# UTN-ESINT01.net
KiCad netlist of a schematic drawn in EAGLE
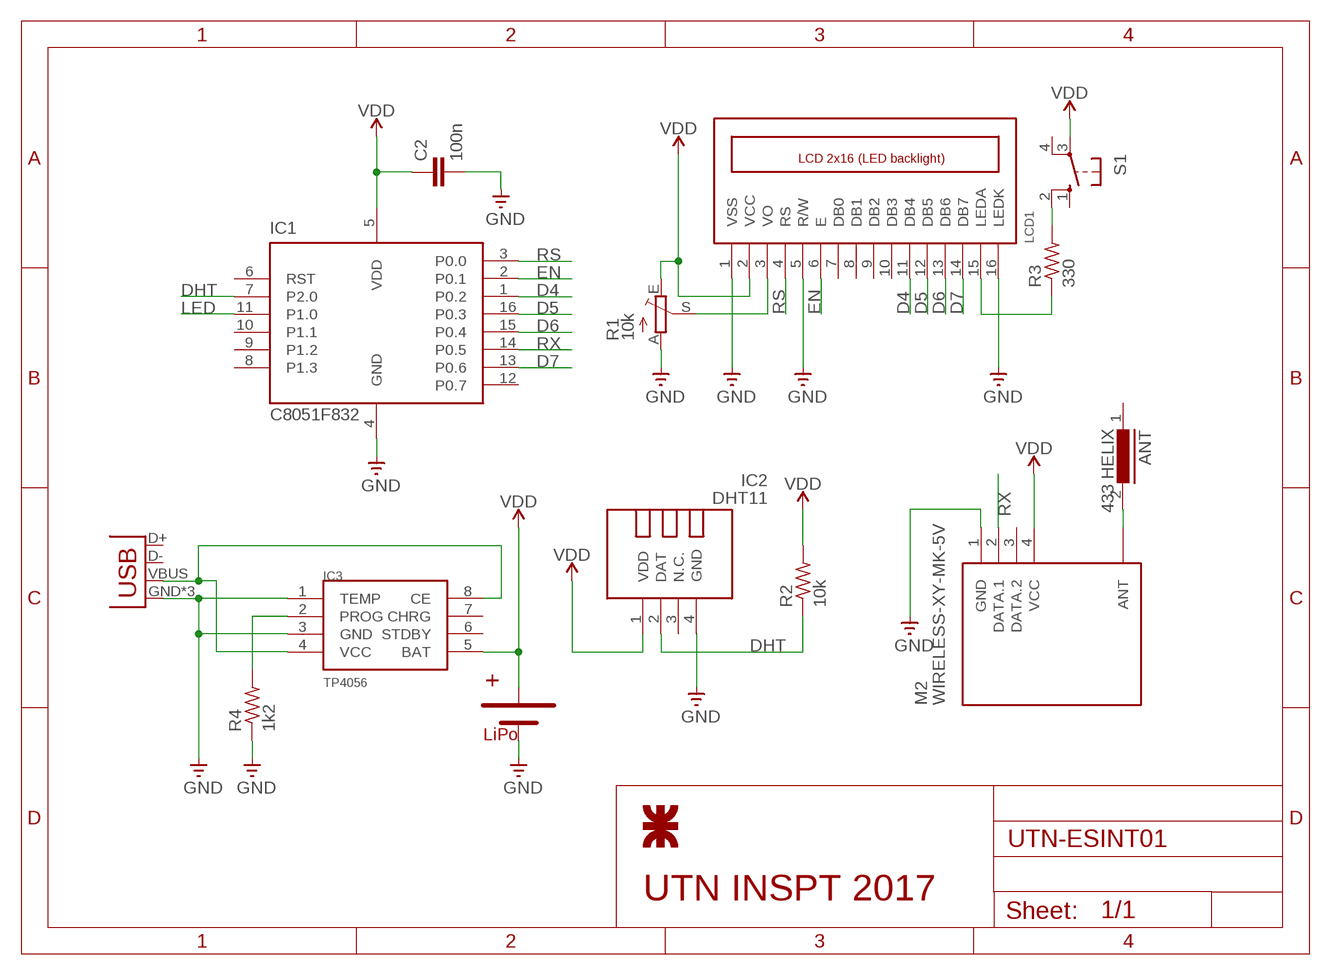
[diagram p0: schematic, sheet 1]

(export (version "E")
  (design (tool "Eeschema 10.0.6"))
  (components
    (comp (ref "ANT")
      (value "433 HELIX")
      (footprint "eagle-import:SMSC20")
      (libsource (lib "eagle-import") (part "SMSC20"))
    )
    (comp (ref "C2")
      (value "100n")
      (footprint "eagle-import:C050-024X044")
      (libsource (lib "eagle-import") (part "C-EU050-024X044"))
    )
    (comp (ref "IC1")
      (value "C8051F832")
      (footprint "eagle-import:SOIC16R")
      (libsource (lib "eagle-import") (part "C8051F832"))
    )
    (comp (ref "IC2")
      (value "DHT11")
      (footprint "eagle-import:TEMP-HUM-SENSOR-DHT11")
      (libsource (lib "eagle-import") (part "TEMP-HUM-SENSOR-DHT11"))
    )
    (comp (ref "IC3")
      (value "TP4056")
      (footprint "eagle-import:SOP-8")
      (libsource (lib "eagle-import") (part "TP4056"))
    )
    (comp (ref "LCD1")
      (value "LCD_2X16_SIL")
      (footprint "eagle-import:HY-1602F")
      (libsource (lib "eagle-import") (part "LCD_2X16_SIL"))
    )
    (comp (ref "M2")
      (value "WIRELESS-XY-MK-5V")
      (footprint "eagle-import:WIRELESS-XY-MK-5V")
      (libsource (lib "eagle-import") (part "WIRELESS-XY-MK-5V"))
    )
    (comp (ref "R1")
      (value "10k")
      (footprint "eagle-import:B64Y")
      (libsource (lib "eagle-import") (part "TRIM_EU-B64Y"))
    )
    (comp (ref "R2")
      (value "10k")
      (footprint "eagle-import:0207_10")
      (libsource (lib "eagle-import") (part "R-US_0207/10"))
    )
    (comp (ref "R3")
      (value "330")
      (footprint "eagle-import:0207_10")
      (libsource (lib "eagle-import") (part "R-US_0207/10"))
    )
    (comp (ref "R4")
      (value "1k2")
      (footprint "eagle-import:0207_10")
      (libsource (lib "eagle-import") (part "R-US_0207/10"))
    )
    (comp (ref "S1")
      (value "10-XX")
      (footprint "eagle-import:B3F-10XX")
      (fields (field (name "MPN") "B3F-1000"))
      (libsource (lib "eagle-import") (part "10-XX"))
    )
    (comp (ref "U$3")
      (value "UTN_LOGO")
      (footprint "eagle-import:UTN_LOGO")
      (libsource (lib "eagle-import") (part "UTN_LOGO"))
    )
    (comp (ref "U$4")
      (value "LiPo")
      (footprint "eagle-import:BATTERYPAD")
      (libsource (lib "eagle-import") (part "BATTERYPAD"))
    )
    (comp (ref "X1")
      (value "USB-MICROB")
      (footprint "eagle-import:USB-MICROB")
      (libsource (lib "eagle-import") (part "USB-MICROB"))
    )
  )
  (nets
    (net (code "1") (name "/D4") (class "Default")
      (node (ref "IC1") (pin "1") (pinfunction "P0.2_1") (pintype "bidirectional"))
      (node (ref "LCD1") (pin "11") (pinfunction "DB4_11") (pintype "bidirectional"))
    )
    (net (code "2") (name "/D5") (class "Default")
      (node (ref "IC1") (pin "16") (pinfunction "P0.3_16") (pintype "bidirectional"))
      (node (ref "LCD1") (pin "12") (pinfunction "DB5_12") (pintype "bidirectional"))
    )
    (net (code "3") (name "/D6") (class "Default")
      (node (ref "IC1") (pin "15") (pinfunction "P0.4_15") (pintype "bidirectional"))
      (node (ref "LCD1") (pin "13") (pinfunction "DB6_13") (pintype "bidirectional"))
    )
    (net (code "4") (name "/D7") (class "Default")
      (node (ref "IC1") (pin "13") (pinfunction "P0.6_13") (pintype "bidirectional"))
      (node (ref "LCD1") (pin "14") (pinfunction "DB7_14") (pintype "bidirectional"))
    )
    (net (code "5") (name "/DHT") (class "Default")
      (node (ref "IC1") (pin "7") (pinfunction "P2.0_7") (pintype "bidirectional"))
      (node (ref "IC2") (pin "2") (pinfunction "DAT_2") (pintype "bidirectional"))
      (node (ref "R2") (pin "1") (pinfunction "1_1") (pintype "passive"))
    )
    (net (code "6") (name "/EN") (class "Default")
      (node (ref "IC1") (pin "2") (pinfunction "P0.1_2") (pintype "bidirectional"))
      (node (ref "LCD1") (pin "6") (pinfunction "E_6") (pintype "input"))
    )
    (net (code "7") (name "/LED") (class "Default")
      (node (ref "IC1") (pin "11") (pinfunction "P1.0_11") (pintype "bidirectional"))
    )
    (net (code "8") (name "/RS") (class "Default")
      (node (ref "IC1") (pin "3") (pinfunction "P0.0_3") (pintype "bidirectional"))
      (node (ref "LCD1") (pin "4") (pinfunction "RS_4") (pintype "input"))
    )
    (net (code "9") (name "/RX") (class "Default")
      (node (ref "IC1") (pin "14") (pinfunction "P0.5_14") (pintype "bidirectional"))
      (node (ref "M2") (pin "2") (pinfunction "DATA.1_2") (pintype "bidirectional"))
    )
    (net (code "10") (name "GND") (class "Default")
      (node (ref "C2") (pin "2") (pinfunction "2_2") (pintype "passive"))
      (node (ref "IC1") (pin "4") (pinfunction "GND_4") (pintype "bidirectional"))
      (node (ref "IC2") (pin "4") (pinfunction "GND_4") (pintype "power_in"))
      (node (ref "IC3") (pin "1") (pinfunction "TEMP_1") (pintype "bidirectional"))
      (node (ref "IC3") (pin "3") (pinfunction "GND_3") (pintype "bidirectional"))
      (node (ref "LCD1") (pin "1") (pinfunction "VSS_1") (pintype "power_in"))
      (node (ref "LCD1") (pin "16") (pinfunction "LEDK_16") (pintype "passive"))
      (node (ref "LCD1") (pin "5") (pinfunction "R/W_5") (pintype "input"))
      (node (ref "M2") (pin "1") (pinfunction "GND_1") (pintype "bidirectional"))
      (node (ref "R1") (pin "A") (pinfunction "A_A") (pintype "passive"))
      (node (ref "R4") (pin "1") (pinfunction "1_1") (pintype "passive"))
      (node (ref "U$4") (pin "-VE") (pinfunction "-VE_-VE") (pintype "power_in"))
      (node (ref "X1") (pin "GND") (pinfunction "GND_GND") (pintype "bidirectional"))
      (node (ref "X1") (pin "MT1") (pinfunction "GND_MT1") (pintype "bidirectional"))
      (node (ref "X1") (pin "MT2") (pinfunction "GND_MT2") (pintype "bidirectional"))
    )
    (net (code "11") (name "Net-(ANT-Pad2)") (class "Default")
      (node (ref "ANT") (pin "2") (pinfunction "2_2") (pintype "passive"))
      (node (ref "M2") (pin "ANT") (pinfunction "ANT_ANT") (pintype "output"))
    )
    (net (code "12") (name "Net-(IC3-CE)") (class "Default")
      (node (ref "IC3") (pin "4") (pinfunction "VCC_4") (pintype "bidirectional"))
      (node (ref "IC3") (pin "8") (pinfunction "CE_8") (pintype "bidirectional"))
      (node (ref "X1") (pin "VBUS") (pinfunction "VBUS_VBUS") (pintype "bidirectional"))
    )
    (net (code "13") (name "Net-(IC3-PROG)") (class "Default")
      (node (ref "IC3") (pin "2") (pinfunction "PROG_2") (pintype "bidirectional"))
      (node (ref "R4") (pin "2") (pinfunction "2_2") (pintype "passive"))
    )
    (net (code "14") (name "Net-(LCD1-LEDA)") (class "Default")
      (node (ref "LCD1") (pin "15") (pinfunction "LEDA_15") (pintype "passive"))
      (node (ref "R3") (pin "1") (pinfunction "1_1") (pintype "passive"))
    )
    (net (code "15") (name "Net-(LCD1-VO)") (class "Default")
      (node (ref "LCD1") (pin "3") (pinfunction "VO_3") (pintype "input"))
      (node (ref "R1") (pin "S") (pinfunction "S_S") (pintype "passive"))
    )
    (net (code "16") (name "Net-(S1-S1)") (class "Default")
      (node (ref "R3") (pin "2") (pinfunction "2_2") (pintype "passive"))
      (node (ref "S1") (pin "2") (pinfunction "S1_2") (pintype "passive"))
    )
    (net (code "17") (name "VDD") (class "Default")
      (node (ref "C2") (pin "1") (pinfunction "1_1") (pintype "passive"))
      (node (ref "IC1") (pin "5") (pinfunction "VDD_5") (pintype "bidirectional"))
      (node (ref "IC2") (pin "1") (pinfunction "VDD_1") (pintype "power_in"))
      (node (ref "IC3") (pin "5") (pinfunction "BAT_5") (pintype "bidirectional"))
      (node (ref "LCD1") (pin "2") (pinfunction "VCC_2") (pintype "power_in"))
      (node (ref "M2") (pin "4") (pinfunction "VCC_4") (pintype "bidirectional"))
      (node (ref "R1") (pin "E") (pinfunction "E_E") (pintype "passive"))
      (node (ref "R2") (pin "2") (pinfunction "2_2") (pintype "passive"))
      (node (ref "S1") (pin "3") (pinfunction "P_3") (pintype "passive"))
      (node (ref "U$4") (pin "+VE") (pinfunction "+VE_+VE") (pintype "power_in"))
    )
    (net (code "18") (name "unconnected-(ANT-Pad1)") (class "Default")
      (node (ref "ANT") (pin "1") (pinfunction "1_1") (pintype "passive"))
    )
    (net (code "19") (name "unconnected-(IC1-P0.7-Pad12)") (class "Default")
      (node (ref "IC1") (pin "12") (pinfunction "P0.7_12") (pintype "bidirectional"))
    )
    (net (code "20") (name "unconnected-(IC1-P1.1-Pad10)") (class "Default")
      (node (ref "IC1") (pin "10") (pinfunction "P1.1_10") (pintype "bidirectional"))
    )
    (net (code "21") (name "unconnected-(IC1-P1.2-Pad9)") (class "Default")
      (node (ref "IC1") (pin "9") (pinfunction "P1.2_9") (pintype "bidirectional"))
    )
    (net (code "22") (name "unconnected-(IC1-P1.3-Pad8)") (class "Default")
      (node (ref "IC1") (pin "8") (pinfunction "P1.3_8") (pintype "bidirectional"))
    )
    (net (code "23") (name "unconnected-(IC1-RST-Pad6)") (class "Default")
      (node (ref "IC1") (pin "6") (pinfunction "RST_6") (pintype "bidirectional"))
    )
    (net (code "24") (name "unconnected-(IC2-N.C.-Pad3)") (class "Default")
      (node (ref "IC2") (pin "3") (pinfunction "N.C._3") (pintype "passive"))
    )
    (net (code "25") (name "unconnected-(IC3-CHRG-Pad7)") (class "Default")
      (node (ref "IC3") (pin "7") (pinfunction "CHRG_7") (pintype "bidirectional"))
    )
    (net (code "26") (name "unconnected-(IC3-STDBY-Pad6)") (class "Default")
      (node (ref "IC3") (pin "6") (pinfunction "STDBY_6") (pintype "bidirectional"))
    )
    (net (code "27") (name "unconnected-(LCD1-DB0-Pad7)") (class "Default")
      (node (ref "LCD1") (pin "7") (pinfunction "DB0_7") (pintype "bidirectional"))
    )
    (net (code "28") (name "unconnected-(LCD1-DB1-Pad8)") (class "Default")
      (node (ref "LCD1") (pin "8") (pinfunction "DB1_8") (pintype "bidirectional"))
    )
    (net (code "29") (name "unconnected-(LCD1-DB2-Pad9)") (class "Default")
      (node (ref "LCD1") (pin "9") (pinfunction "DB2_9") (pintype "bidirectional"))
    )
    (net (code "30") (name "unconnected-(LCD1-DB3-Pad10)") (class "Default")
      (node (ref "LCD1") (pin "10") (pinfunction "DB3_10") (pintype "bidirectional"))
    )
    (net (code "31") (name "unconnected-(M2-DATA.2-Pad3)") (class "Default")
      (node (ref "M2") (pin "3") (pinfunction "DATA.2_3") (pintype "bidirectional"))
    )
    (net (code "32") (name "unconnected-(S1-P1-Pad4)") (class "Default")
      (node (ref "S1") (pin "4") (pinfunction "P1_4") (pintype "passive"))
    )
    (net (code "33") (name "unconnected-(S1-S-Pad1)") (class "Default")
      (node (ref "S1") (pin "1") (pinfunction "S_1") (pintype "passive"))
    )
    (net (code "34") (name "unconnected-(X1-PadD+)") (class "Default")
      (node (ref "X1") (pin "D+") (pinfunction "D+_D+") (pintype "bidirectional"))
    )
    (net (code "35") (name "unconnected-(X1-PadD-)") (class "Default")
      (node (ref "X1") (pin "D-") (pinfunction "D-_D-") (pintype "bidirectional"))
    )
  )
)
